# AD.net
KiCad netlist of a schematic drawn in Altium Designer
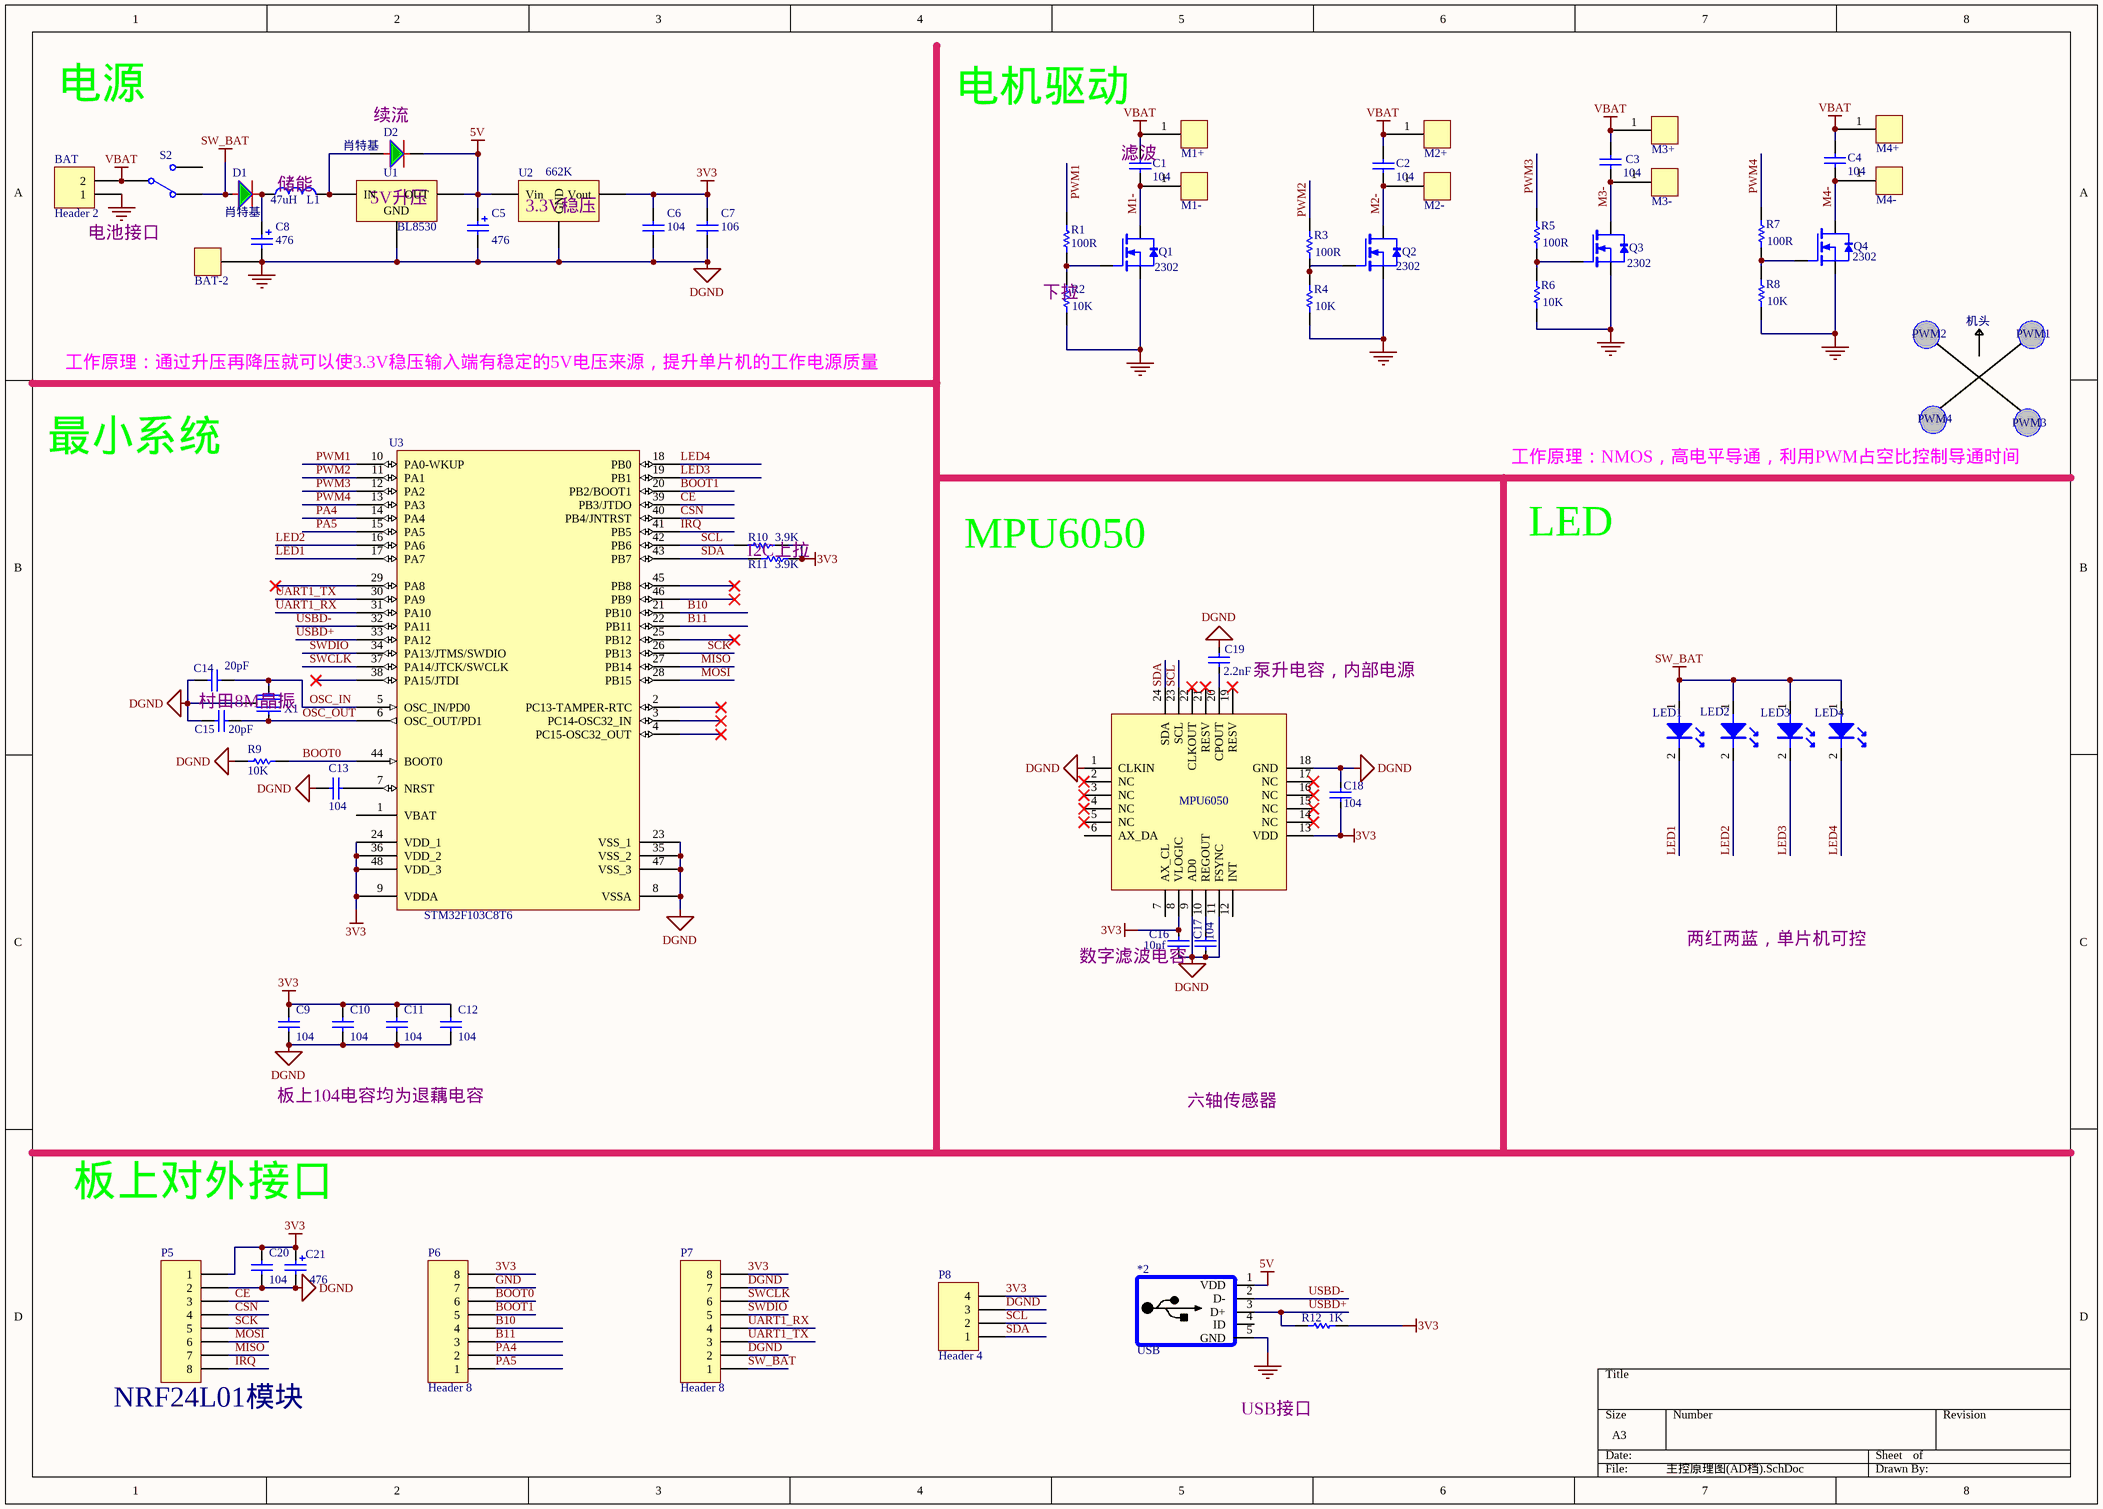
[diagram p0: 主控原理图(AD档).SchDoc]

(export (version "E")
  (design (tool "Eeschema 10.0.6"))
  (components
    (comp (ref "*2") (value "USB") (footprint "USB") (libsource (lib "电子鼓") (part "USB")))
    (comp (ref "BAT")
      (value "Header 2")
      (footprint "HDR2")
      (description "Header, 2-Pin")
      (fields (field (name "PUBLISHER") "Altium Limited"))
      (libsource (lib "Miscellaneous Connectors") (part "Header 2"))
    )
    (comp (ref "BAT-2") (value "Header 1") (footprint "电池接口") (libsource (lib "") (part "Header 1_1")))
    (comp (ref "C1")
      (value "104")
      (footprint "0603C")
      (description "Polarized Capacitor (Radial)")
      (fields (field (name "Comment") "Cap Chip 1206") (field (name "PUBLISHER") "Altium Limited"))
      (libsource (lib "ChapuIntegratedLibrary") (part "Cap Chip 1206"))
    )
    (comp (ref "C2")
      (value "104")
      (footprint "0603C")
      (description "Polarized Capacitor (Radial)")
      (fields (field (name "PUBLISHER") "Altium Limited"))
      (libsource (lib "ChapuIntegratedLibrary") (part "Cap Chip 1206"))
    )
    (comp (ref "C3")
      (value "104")
      (footprint "0603C")
      (description "Polarized Capacitor (Radial)")
      (fields (field (name "Comment") "Cap Chip 1206") (field (name "PUBLISHER") "Altium Limited"))
      (libsource (lib "ChapuIntegratedLibrary") (part "Cap Chip 1206"))
    )
    (comp (ref "C4")
      (value "104")
      (footprint "0603C")
      (description "Polarized Capacitor (Radial)")
      (fields (field (name "Comment") "Cap Chip 1206") (field (name "PUBLISHER") "Altium Limited"))
      (libsource (lib "ChapuIntegratedLibrary") (part "Cap Chip 1206"))
    )
    (comp (ref "C5")
      (value "476")
      (footprint "1206c")
      (description "Polarized Capacitor (Radial)")
      (fields
        (field (name "VOLTAGE") "16V")
        (field (name "Comment") "Cap Tan A")
        (field (name "PUBLISHER") "Altium Limited")
      )
      (libsource (lib "ChapuIntegratedLibrary") (part "Cap Tan A"))
    )
    (comp (ref "C6")
      (value "104")
      (footprint "0603C")
      (description "Polarized Capacitor (Radial)")
      (fields (field (name "Comment") "Cap Chip 1206") (field (name "PUBLISHER") "Altium Limited"))
      (libsource (lib "ChapuIntegratedLibrary") (part "Cap Chip 1206"))
    )
    (comp (ref "C7")
      (value "106")
      (footprint "0603c")
      (description "Polarized Capacitor (Radial)")
      (fields (field (name "Comment") "Cap Chip 1206") (field (name "PUBLISHER") "Altium Limited"))
      (libsource (lib "ChapuIntegratedLibrary") (part "Cap Chip 1206"))
    )
    (comp (ref "C8")
      (value "476")
      (footprint "1206c")
      (description "Polarized Capacitor (Radial)")
      (fields
        (field (name "VOLTAGE") "16V")
        (field (name "Comment") "Cap Tan A")
        (field (name "PUBLISHER") "Altium Limited")
      )
      (libsource (lib "ChapuIntegratedLibrary") (part "Cap Tan A"))
    )
    (comp (ref "C9") (value "104") (footprint "0603C") (libsource (lib "1218迷你四轴工程_1") (part "C0603")))
    (comp (ref "C10") (value "104") (footprint "0603C") (libsource (lib "1218迷你四轴工程_1") (part "C0603")))
    (comp (ref "C11") (value "104") (footprint "0603C") (libsource (lib "1218迷你四轴工程_1") (part "C0603")))
    (comp (ref "C12") (value "104") (footprint "0603C") (libsource (lib "1218迷你四轴工程_1") (part "C0603")))
    (comp (ref "C13") (value "104") (footprint "0603C") (libsource (lib "1218迷你四轴工程_1") (part "C0603")))
    (comp (ref "C14") (value "20pF") (footprint "0603C") (libsource (lib "1218迷你四轴工程_1") (part "C0603")))
    (comp (ref "C15") (value "20pF") (footprint "0603C") (libsource (lib "1218迷你四轴工程_1") (part "C0603")))
    (comp (ref "C16")
      (value "10nf")
      (footprint "0603C")
      (description "Capacitor")
      (fields (field (name "Comment") "Cap_0603"))
      (libsource (lib "SCH_Passive") (part "Cap_0603"))
    )
    (comp (ref "C17")
      (value "104")
      (footprint "0603C")
      (description "Capacitor")
      (fields (field (name "Comment") "Cap_0603"))
      (libsource (lib "SCH_Passive") (part "Cap_0603"))
    )
    (comp (ref "C18")
      (value "104")
      (footprint "0603C")
      (description "Capacitor")
      (fields (field (name "Comment") "Cap_0603"))
      (libsource (lib "SCH_Passive") (part "Cap_0603"))
    )
    (comp (ref "C19")
      (value "2.2nF")
      (footprint "0603C")
      (description "Capacitor")
      (fields (field (name "Comment") "Cap_0603"))
      (libsource (lib "SCH_Passive") (part "Cap_0603"))
    )
    (comp (ref "C20") (value "104") (footprint "0603C") (libsource (lib "1218迷你四轴工程_1") (part "C0603")))
    (comp (ref "C21")
      (value "476")
      (footprint "1206c")
      (description "Polarized Capacitor (Radial)")
      (fields
        (field (name "VOLTAGE") "16V")
        (field (name "Comment") "Cap Tan A")
        (field (name "PUBLISHER") "Altium Limited")
      )
      (libsource (lib "ChapuIntegratedLibrary") (part "Cap Tan A"))
    )
    (comp (ref "D1") (value "肖特基") (footprint "0805d") (libsource (lib "*") (part "DIODE")))
    (comp (ref "D2") (value "肖特基") (footprint "0805d") (libsource (lib "") (part "DIODE_1")))
    (comp (ref "L1")
      (value "47uH")
      (footprint "电感")
      (description "Inductor")
      (fields (field (name "Comment") "Inductor Chip") (field (name "PUBLISHER") "Altium Limited"))
      (libsource (lib "ChapuIntegratedLibrary") (part "Inductor Chip"))
    )
    (comp (ref "LED1") (value "LED") (footprint "0603D") (libsource (lib "1218迷你四轴工程_1") (part "LED")))
    (comp (ref "LED2") (value "LED") (footprint "0603D") (libsource (lib "1218迷你四轴工程_1") (part "LED")))
    (comp (ref "LED3") (value "LED") (footprint "0603D") (libsource (lib "1218迷你四轴工程_1") (part "LED")))
    (comp (ref "LED4") (value "LED") (footprint "0603D") (libsource (lib "1218迷你四轴工程_1") (part "LED")))
    (comp (ref "M1+") (value "Header 1") (footprint "电池接口") (libsource (lib "quadrotor") (part "Header 1")))
    (comp (ref "M1-") (value "Header 1") (footprint "电池接口") (libsource (lib "quadrotor") (part "Header 1")))
    (comp (ref "M2+") (value "Header 1") (footprint "电池接口") (libsource (lib "quadrotor") (part "Header 1")))
    (comp (ref "M2-") (value "Header 1") (footprint "电池接口") (libsource (lib "quadrotor") (part "Header 1")))
    (comp (ref "M3+") (value "Header 1") (footprint "电池接口") (libsource (lib "quadrotor") (part "Header 1")))
    (comp (ref "M3-") (value "Header 1") (footprint "电池接口") (libsource (lib "quadrotor") (part "Header 1")))
    (comp (ref "M4+") (value "Header 1") (footprint "电池接口") (libsource (lib "quadrotor") (part "Header 1")))
    (comp (ref "M4-") (value "Header 1") (footprint "电池接口") (libsource (lib "quadrotor") (part "Header 1")))
    (comp (ref "P5")
      (value "NRF24L01模块")
      (footprint "2.4G")
      (description "Header, 8-Pin")
      (fields (field (name "PUBLISHER") "Altium Limited"))
      (libsource (lib "Miscellaneous Connectors") (part "Header 8"))
    )
    (comp (ref "P6")
      (value "Header 8")
      (footprint "HDR8")
      (description "Header, 8-Pin")
      (fields (field (name "PUBLISHER") "Altium Limited"))
      (libsource (lib "") (part "Header 8_1"))
    )
    (comp (ref "P7")
      (value "Header 8")
      (footprint "HDR8")
      (description "Header, 8-Pin")
      (fields (field (name "PUBLISHER") "Altium Limited"))
      (libsource (lib "") (part "Header 8_1"))
    )
    (comp (ref "P8")
      (value "Header 4")
      (footprint "HDR4")
      (description "Header, 4-Pin")
      (fields (field (name "PUBLISHER") "Altium Limited"))
      (libsource (lib "Miscellaneous Connectors") (part "Header 4"))
    )
    (comp (ref "Q1")
      (value "2302")
      (footprint "NMOS")
      (description "N-Channel MOSFET")
      (libsource (lib "1218迷你四轴工程_1") (part "N_MOS"))
    )
    (comp (ref "Q2")
      (value "2302")
      (footprint "NMOS")
      (description "N-Channel Power MOSFET")
      (libsource (lib "1218迷你四轴工程_1") (part "N_MOS"))
    )
    (comp (ref "Q3")
      (value "2302")
      (footprint "NMOS")
      (description "N-Channel Power MOSFET")
      (libsource (lib "1218迷你四轴工程_1") (part "N_MOS"))
    )
    (comp (ref "Q4")
      (value "2302")
      (footprint "NMOS")
      (description "N-Channel Power MOSFET")
      (libsource (lib "1218迷你四轴工程_1") (part "N_MOS"))
    )
    (comp (ref "R1")
      (value "100R")
      (footprint "0603R")
      (description "Resistor")
      (fields (field (name "Comment") "Res1") (field (name "PUBLISHER") "Altium Limited"))
      (libsource (lib "Miscellaneous Devices") (part "Res1"))
    )
    (comp (ref "R2")
      (value "10K")
      (footprint "0603R")
      (description "Resistor")
      (fields (field (name "Comment") "Res1") (field (name "PUBLISHER") "Altium Limited"))
      (libsource (lib "Miscellaneous Devices") (part "Res1"))
    )
    (comp (ref "R3")
      (value "100R")
      (footprint "0603R")
      (description "Resistor")
      (fields (field (name "Comment") "Res1") (field (name "PUBLISHER") "Altium Limited"))
      (libsource (lib "Miscellaneous Devices") (part "Res1"))
    )
    (comp (ref "R4")
      (value "10K")
      (footprint "0603R")
      (description "Resistor")
      (fields (field (name "Comment") "Res1") (field (name "PUBLISHER") "Altium Limited"))
      (libsource (lib "Miscellaneous Devices") (part "Res1"))
    )
    (comp (ref "R5")
      (value "100R")
      (footprint "0603R")
      (description "Resistor")
      (fields (field (name "Comment") "Res1") (field (name "PUBLISHER") "Altium Limited"))
      (libsource (lib "Miscellaneous Devices") (part "Res1"))
    )
    (comp (ref "R6")
      (value "10K")
      (footprint "0603R")
      (description "Resistor")
      (fields (field (name "Comment") "Res1") (field (name "PUBLISHER") "Altium Limited"))
      (libsource (lib "Miscellaneous Devices") (part "Res1"))
    )
    (comp (ref "R7")
      (value "100R")
      (footprint "0603R")
      (description "Resistor")
      (fields (field (name "Comment") "Res1") (field (name "PUBLISHER") "Altium Limited"))
      (libsource (lib "Miscellaneous Devices") (part "Res1"))
    )
    (comp (ref "R8")
      (value "10K")
      (footprint "0603R")
      (description "Resistor")
      (fields (field (name "Comment") "Res1") (field (name "PUBLISHER") "Altium Limited"))
      (libsource (lib "Miscellaneous Devices") (part "Res1"))
    )
    (comp (ref "R9")
      (value "10K")
      (footprint "0603R")
      (description "Resistor")
      (fields (field (name "Comment") "Res1") (field (name "PUBLISHER") "Altium Limited"))
      (libsource (lib "Miscellaneous Devices") (part "Res1"))
    )
    (comp (ref "R10")
      (value "3.9K")
      (footprint "0603R")
      (description "Resistor")
      (fields (field (name "Comment") "Res1") (field (name "PUBLISHER") "Altium Limited"))
      (libsource (lib "Miscellaneous Devices") (part "Res1"))
    )
    (comp (ref "R11")
      (value "3.9K")
      (footprint "0603R")
      (description "Resistor")
      (fields (field (name "Comment") "Res1") (field (name "PUBLISHER") "Altium Limited"))
      (libsource (lib "Miscellaneous Devices") (part "Res1"))
    )
    (comp (ref "R12")
      (value "1K")
      (footprint "0603R")
      (description "Resistor")
      (fields (field (name "Comment") "Res1") (field (name "PUBLISHER") "Altium Limited"))
      (libsource (lib "Miscellaneous Devices") (part "Res1"))
    )
    (comp (ref "S2")
      (value "SW-SPDT")
      (footprint "SWITCH")
      (description "SPDT Subminiature Toggle Switch, Right Angle Mounting, Vertical Actuation")
      (fields (field (name "PUBLISHER") "Altium Limited"))
      (libsource (lib "Miscellaneous Devices") (part "SW-SPDT"))
    )
    (comp (ref "U1")
      (value "BL8530")
      (footprint "SOT-89")
      (description "POSITIVE OUTPUT VOLTAGE")
      (libsource (lib "Q222") (part "HT7750"))
    )
    (comp (ref "U2")
      (value "662K")
      (footprint "LDO")
      (description "3-Terminal Adjustable Positive Voltage Regulator")
      (libsource (lib "稳压器件") (part "LM317"))
    )
    (comp (ref "U3")
      (value "STM32F103C8T6")
      (footprint "LQFP48")
      (libsource (lib "微型四轴") (part "STM32F103C8T6"))
    )
    (comp (ref "U8") (value "MPU6050") (footprint "QFN24") (libsource (lib "1218迷你四轴工程_1") (part "MPU6050")))
    (comp (ref "X1") (value "XTAL_SMT") (footprint "OSC") (libsource (lib "dx原理图库") (part "XTAL_SMT")))
  )
  (nets
    (net (code "1") (name "/B10") (class "Default")
      (node (ref "P6") (pin "4") (pinfunction "4_4") (pintype "passive"))
      (node (ref "U3") (pin "21") (pinfunction "PB10_21") (pintype "bidirectional"))
    )
    (net (code "2") (name "/B11") (class "Default")
      (node (ref "P6") (pin "3") (pinfunction "3_3") (pintype "passive"))
      (node (ref "U3") (pin "22") (pinfunction "PB11_22") (pintype "bidirectional"))
    )
    (net (code "3") (name "/BOOT0") (class "Default")
      (node (ref "P6") (pin "6") (pinfunction "6_6") (pintype "passive"))
      (node (ref "R9") (pin "1") (pinfunction "1_1") (pintype "passive"))
      (node (ref "U3") (pin "44") (pinfunction "BOOT0_44") (pintype "input"))
    )
    (net (code "4") (name "/BOOT1") (class "Default")
      (node (ref "P6") (pin "5") (pinfunction "5_5") (pintype "passive"))
      (node (ref "U3") (pin "20") (pinfunction "PB2/BOOT1_20") (pintype "bidirectional"))
    )
    (net (code "5") (name "/CE") (class "Default")
      (node (ref "P5") (pin "3") (pinfunction "3_3") (pintype "passive"))
      (node (ref "U3") (pin "39") (pinfunction "PB3/JTDO_39") (pintype "bidirectional"))
    )
    (net (code "6") (name "/CSN") (class "Default")
      (node (ref "P5") (pin "4") (pinfunction "4_4") (pintype "passive"))
      (node (ref "U3") (pin "40") (pinfunction "PB4/JNTRST_40") (pintype "bidirectional"))
    )
    (net (code "7") (name "/IRQ") (class "Default")
      (node (ref "P5") (pin "8") (pinfunction "8_8") (pintype "passive"))
      (node (ref "U3") (pin "41") (pinfunction "PB5_41") (pintype "bidirectional"))
    )
    (net (code "8") (name "/LED1") (class "Default")
      (node (ref "LED1") (pin "2") (pinfunction "2_2") (pintype "passive"))
      (node (ref "U3") (pin "17") (pinfunction "PA7_17") (pintype "bidirectional"))
    )
    (net (code "9") (name "/LED2") (class "Default")
      (node (ref "LED2") (pin "2") (pinfunction "2_2") (pintype "passive"))
      (node (ref "U3") (pin "16") (pinfunction "PA6_16") (pintype "bidirectional"))
    )
    (net (code "10") (name "/LED3") (class "Default")
      (node (ref "LED3") (pin "2") (pinfunction "2_2") (pintype "passive"))
      (node (ref "U3") (pin "19") (pinfunction "PB1_19") (pintype "bidirectional"))
    )
    (net (code "11") (name "/LED4") (class "Default")
      (node (ref "LED4") (pin "2") (pinfunction "2_2") (pintype "passive"))
      (node (ref "U3") (pin "18") (pinfunction "PB0_18") (pintype "bidirectional"))
    )
    (net (code "12") (name "/M1-") (class "Default")
      (node (ref "C1") (pin "1") (pinfunction "1_1") (pintype "passive"))
      (node (ref "M1-") (pin "1") (pintype "passive"))
      (node (ref "Q1") (pin "2") (pinfunction "D_2") (pintype "passive"))
    )
    (net (code "13") (name "/M2-") (class "Default")
      (node (ref "C2") (pin "1") (pinfunction "1_1") (pintype "passive"))
      (node (ref "M2-") (pin "1") (pintype "passive"))
      (node (ref "Q2") (pin "2") (pinfunction "D_2") (pintype "passive"))
    )
    (net (code "14") (name "/M3-") (class "Default")
      (node (ref "C3") (pin "1") (pinfunction "1_1") (pintype "passive"))
      (node (ref "M3-") (pin "1") (pintype "passive"))
      (node (ref "Q3") (pin "2") (pinfunction "D_2") (pintype "passive"))
    )
    (net (code "15") (name "/M4-") (class "Default")
      (node (ref "C4") (pin "1") (pinfunction "1_1") (pintype "passive"))
      (node (ref "M4-") (pin "1") (pintype "passive"))
      (node (ref "Q4") (pin "2") (pinfunction "D_2") (pintype "passive"))
    )
    (net (code "16") (name "/MISO") (class "Default")
      (node (ref "P5") (pin "7") (pinfunction "7_7") (pintype "passive"))
      (node (ref "U3") (pin "27") (pinfunction "PB14_27") (pintype "bidirectional"))
    )
    (net (code "17") (name "/MOSI") (class "Default")
      (node (ref "P5") (pin "6") (pinfunction "6_6") (pintype "passive"))
      (node (ref "U3") (pin "28") (pinfunction "PB15_28") (pintype "bidirectional"))
    )
    (net (code "18") (name "/OSC_IN") (class "Default")
      (node (ref "C14") (pin "1") (pinfunction "1_1") (pintype "passive"))
      (node (ref "U3") (pin "5") (pinfunction "OSC_IN/PD0_5") (pintype "input"))
      (node (ref "X1") (pin "2") (pintype "passive"))
    )
    (net (code "19") (name "/OSC_OUT") (class "Default")
      (node (ref "C15") (pin "1") (pinfunction "1_1") (pintype "passive"))
      (node (ref "U3") (pin "6") (pinfunction "OSC_OUT/PD1_6") (pintype "output"))
      (node (ref "X1") (pin "1") (pintype "passive"))
    )
    (net (code "20") (name "/PA4") (class "Default")
      (node (ref "P6") (pin "2") (pinfunction "2_2") (pintype "passive"))
      (node (ref "U3") (pin "14") (pinfunction "PA4_14") (pintype "bidirectional"))
    )
    (net (code "21") (name "/PA5") (class "Default")
      (node (ref "P6") (pin "1") (pinfunction "1_1") (pintype "passive"))
      (node (ref "U3") (pin "15") (pinfunction "PA5_15") (pintype "bidirectional"))
    )
    (net (code "22") (name "/PWM1") (class "Default")
      (node (ref "R1") (pin "2") (pinfunction "2_2") (pintype "passive"))
      (node (ref "U3") (pin "10") (pinfunction "PA0-WKUP_10") (pintype "bidirectional"))
    )
    (net (code "23") (name "/PWM2") (class "Default")
      (node (ref "R3") (pin "2") (pinfunction "2_2") (pintype "passive"))
      (node (ref "U3") (pin "11") (pinfunction "PA1_11") (pintype "bidirectional"))
    )
    (net (code "24") (name "/PWM3") (class "Default")
      (node (ref "R5") (pin "2") (pinfunction "2_2") (pintype "passive"))
      (node (ref "U3") (pin "12") (pinfunction "PA2_12") (pintype "bidirectional"))
    )
    (net (code "25") (name "/PWM4") (class "Default")
      (node (ref "R7") (pin "2") (pinfunction "2_2") (pintype "passive"))
      (node (ref "U3") (pin "13") (pinfunction "PA3_13") (pintype "bidirectional"))
    )
    (net (code "26") (name "/SCK") (class "Default")
      (node (ref "P5") (pin "5") (pinfunction "5_5") (pintype "passive"))
      (node (ref "U3") (pin "26") (pinfunction "PB13_26") (pintype "bidirectional"))
    )
    (net (code "27") (name "/SCL") (class "Default")
      (node (ref "P8") (pin "2") (pinfunction "2_2") (pintype "passive"))
      (node (ref "R10") (pin "2") (pinfunction "2_2") (pintype "passive"))
      (node (ref "U3") (pin "42") (pinfunction "PB6_42") (pintype "bidirectional"))
      (node (ref "U8") (pin "23") (pinfunction "SCL_23") (pintype "passive"))
    )
    (net (code "28") (name "/SDA") (class "Default")
      (node (ref "P8") (pin "1") (pinfunction "1_1") (pintype "passive"))
      (node (ref "R11") (pin "2") (pinfunction "2_2") (pintype "passive"))
      (node (ref "U3") (pin "43") (pinfunction "PB7_43") (pintype "bidirectional"))
      (node (ref "U8") (pin "24") (pinfunction "SDA_24") (pintype "passive"))
    )
    (net (code "29") (name "/SWCLK") (class "Default")
      (node (ref "P7") (pin "6") (pinfunction "6_6") (pintype "passive"))
      (node (ref "U3") (pin "37") (pinfunction "PA14/JTCK/SWCLK_37") (pintype "bidirectional"))
    )
    (net (code "30") (name "/SWDIO") (class "Default")
      (node (ref "P7") (pin "5") (pinfunction "5_5") (pintype "passive"))
      (node (ref "U3") (pin "34") (pinfunction "PA13/JTMS/SWDIO_34") (pintype "bidirectional"))
    )
    (net (code "31") (name "/UART1_RX") (class "Default")
      (node (ref "P7") (pin "4") (pinfunction "4_4") (pintype "passive"))
      (node (ref "U3") (pin "31") (pinfunction "PA10_31") (pintype "bidirectional"))
    )
    (net (code "32") (name "/UART1_TX") (class "Default")
      (node (ref "P7") (pin "3") (pinfunction "3_3") (pintype "passive"))
      (node (ref "U3") (pin "30") (pinfunction "PA9_30") (pintype "bidirectional"))
    )
    (net (code "33") (name "/USBD+") (class "Default")
      (node (ref "*2") (pin "3") (pinfunction "D+_3") (pintype "passive"))
      (node (ref "R12") (pin "2") (pinfunction "2_2") (pintype "passive"))
      (node (ref "U3") (pin "33") (pinfunction "PA12_33") (pintype "bidirectional"))
    )
    (net (code "34") (name "/USBD-") (class "Default")
      (node (ref "*2") (pin "2") (pinfunction "D-_2") (pintype "passive"))
      (node (ref "U3") (pin "32") (pinfunction "PA11_32") (pintype "bidirectional"))
    )
    (net (code "35") (name "3V3") (class "Default")
      (node (ref "C10") (pin "1") (pinfunction "1_1") (pintype "passive"))
      (node (ref "C11") (pin "1") (pinfunction "1_1") (pintype "passive"))
      (node (ref "C12") (pin "1") (pinfunction "1_1") (pintype "passive"))
      (node (ref "C16") (pin "2") (pinfunction "2_2") (pintype "passive"))
      (node (ref "C18") (pin "1") (pinfunction "1_1") (pintype "passive"))
      (node (ref "C20") (pin "1") (pinfunction "1_1") (pintype "passive"))
      (node (ref "C21") (pin "2") (pinfunction "1_2") (pintype "passive"))
      (node (ref "C6") (pin "1") (pinfunction "1_1") (pintype "passive"))
      (node (ref "C7") (pin "1") (pinfunction "1_1") (pintype "passive"))
      (node (ref "C9") (pin "1") (pinfunction "1_1") (pintype "passive"))
      (node (ref "P5") (pin "1") (pinfunction "1_1") (pintype "passive"))
      (node (ref "P6") (pin "8") (pinfunction "8_8") (pintype "passive"))
      (node (ref "P7") (pin "8") (pinfunction "8_8") (pintype "passive"))
      (node (ref "P8") (pin "4") (pinfunction "4_4") (pintype "passive"))
      (node (ref "R10") (pin "1") (pinfunction "1_1") (pintype "passive"))
      (node (ref "R11") (pin "1") (pinfunction "1_1") (pintype "passive"))
      (node (ref "R12") (pin "1") (pinfunction "1_1") (pintype "passive"))
      (node (ref "U2") (pin "2") (pinfunction "Vout_2") (pintype "passive"))
      (node (ref "U3") (pin "24") (pinfunction "VDD_1_24") (pintype "power_in"))
      (node (ref "U3") (pin "36") (pinfunction "VDD_2_36") (pintype "power_in"))
      (node (ref "U3") (pin "48") (pinfunction "VDD_3_48") (pintype "power_in"))
      (node (ref "U3") (pin "9") (pinfunction "VDDA_9") (pintype "power_in"))
      (node (ref "U8") (pin "13") (pinfunction "VDD_13") (pintype "passive"))
      (node (ref "U8") (pin "8") (pinfunction "VLOGIC_8") (pintype "passive"))
    )
    (net (code "36") (name "5V") (class "Default")
      (node (ref "*2") (pin "1") (pinfunction "VDD_1") (pintype "passive"))
      (node (ref "C5") (pin "2") (pinfunction "1_2") (pintype "passive"))
      (node (ref "D2") (pin "2") (pinfunction "2_2") (pintype "passive"))
      (node (ref "U1") (pin "2") (pinfunction "OUT_2") (pintype "power_in"))
      (node (ref "U2") (pin "3") (pinfunction "Vin_3") (pintype "passive"))
    )
    (net (code "37") (name "DGND") (class "Default")
      (node (ref "*2") (pin "5") (pinfunction "GND_5") (pintype "passive"))
      (node (ref "BAT") (pin "1") (pinfunction "1_1") (pintype "passive"))
      (node (ref "BAT-2") (pin "1") (pintype "passive"))
      (node (ref "C10") (pin "2") (pinfunction "2_2") (pintype "passive"))
      (node (ref "C11") (pin "2") (pinfunction "2_2") (pintype "passive"))
      (node (ref "C12") (pin "2") (pinfunction "2_2") (pintype "passive"))
      (node (ref "C13") (pin "1") (pinfunction "1_1") (pintype "passive"))
      (node (ref "C14") (pin "2") (pinfunction "2_2") (pintype "passive"))
      (node (ref "C15") (pin "2") (pinfunction "2_2") (pintype "passive"))
      (node (ref "C16") (pin "1") (pinfunction "1_1") (pintype "passive"))
      (node (ref "C17") (pin "1") (pinfunction "1_1") (pintype "passive"))
      (node (ref "C18") (pin "2") (pinfunction "2_2") (pintype "passive"))
      (node (ref "C19") (pin "2") (pinfunction "2_2") (pintype "passive"))
      (node (ref "C20") (pin "2") (pinfunction "2_2") (pintype "passive"))
      (node (ref "C21") (pin "1") (pinfunction "2_1") (pintype "passive"))
      (node (ref "C5") (pin "1") (pinfunction "2_1") (pintype "passive"))
      (node (ref "C6") (pin "2") (pinfunction "2_2") (pintype "passive"))
      (node (ref "C7") (pin "2") (pinfunction "2_2") (pintype "passive"))
      (node (ref "C8") (pin "1") (pinfunction "2_1") (pintype "passive"))
      (node (ref "C9") (pin "2") (pinfunction "2_2") (pintype "passive"))
      (node (ref "P5") (pin "2") (pinfunction "2_2") (pintype "passive"))
      (node (ref "P6") (pin "7") (pinfunction "7_7") (pintype "passive"))
      (node (ref "P7") (pin "2") (pinfunction "2_2") (pintype "passive"))
      (node (ref "P7") (pin "7") (pinfunction "7_7") (pintype "passive"))
      (node (ref "P8") (pin "3") (pinfunction "3_3") (pintype "passive"))
      (node (ref "Q1") (pin "3") (pinfunction "S_3") (pintype "passive"))
      (node (ref "Q2") (pin "3") (pinfunction "S_3") (pintype "passive"))
      (node (ref "Q3") (pin "3") (pinfunction "S_3") (pintype "passive"))
      (node (ref "Q4") (pin "3") (pinfunction "S_3") (pintype "passive"))
      (node (ref "R2") (pin "1") (pinfunction "1_1") (pintype "passive"))
      (node (ref "R4") (pin "1") (pinfunction "1_1") (pintype "passive"))
      (node (ref "R6") (pin "1") (pinfunction "1_1") (pintype "passive"))
      (node (ref "R8") (pin "1") (pinfunction "1_1") (pintype "passive"))
      (node (ref "R9") (pin "2") (pinfunction "2_2") (pintype "passive"))
      (node (ref "U1") (pin "1") (pinfunction "GND_1") (pintype "power_in"))
      (node (ref "U2") (pin "1") (pinfunction "GND_1") (pintype "passive"))
      (node (ref "U3") (pin "23") (pinfunction "VSS_1_23") (pintype "power_in"))
      (node (ref "U3") (pin "35") (pinfunction "VSS_2_35") (pintype "power_in"))
      (node (ref "U3") (pin "47") (pinfunction "VSS_3_47") (pintype "power_in"))
      (node (ref "U3") (pin "8") (pinfunction "VSSA_8") (pintype "power_in"))
      (node (ref "U8") (pin "1") (pinfunction "CLKIN_1") (pintype "passive"))
      (node (ref "U8") (pin "11") (pinfunction "FSYNC_11") (pintype "passive"))
      (node (ref "U8") (pin "18") (pinfunction "GND_18") (pintype "passive"))
      (node (ref "U8") (pin "9") (pinfunction "AD0_9") (pintype "passive"))
      (node (ref "X1") (pin "0") (pinfunction "0_0") (pintype "passive"))
    )
    (net (code "38") (name "Net-(C8-1)") (class "Default")
      (node (ref "C8") (pin "2") (pinfunction "1_2") (pintype "passive"))
      (node (ref "D1") (pin "2") (pinfunction "2_2") (pintype "passive"))
      (node (ref "L1") (pin "1") (pinfunction "1_1") (pintype "passive"))
    )
    (net (code "39") (name "Net-(Q1-G)") (class "Default")
      (node (ref "Q1") (pin "1") (pinfunction "G_1") (pintype "passive"))
      (node (ref "R1") (pin "1") (pinfunction "1_1") (pintype "passive"))
      (node (ref "R2") (pin "2") (pinfunction "2_2") (pintype "passive"))
    )
    (net (code "40") (name "Net-(Q2-G)") (class "Default")
      (node (ref "Q2") (pin "1") (pinfunction "G_1") (pintype "passive"))
      (node (ref "R3") (pin "1") (pinfunction "1_1") (pintype "passive"))
      (node (ref "R4") (pin "2") (pinfunction "2_2") (pintype "passive"))
    )
    (net (code "41") (name "Net-(Q3-G)") (class "Default")
      (node (ref "Q3") (pin "1") (pinfunction "G_1") (pintype "passive"))
      (node (ref "R5") (pin "1") (pinfunction "1_1") (pintype "passive"))
      (node (ref "R6") (pin "2") (pinfunction "2_2") (pintype "passive"))
    )
    (net (code "42") (name "Net-(Q4-G)") (class "Default")
      (node (ref "Q4") (pin "1") (pinfunction "G_1") (pintype "passive"))
      (node (ref "R7") (pin "1") (pinfunction "1_1") (pintype "passive"))
      (node (ref "R8") (pin "2") (pinfunction "2_2") (pintype "passive"))
    )
    (net (code "43") (name "Net-(U1-IN)") (class "Default")
      (node (ref "D2") (pin "1") (pinfunction "1_1") (pintype "passive"))
      (node (ref "L1") (pin "2") (pinfunction "2_2") (pintype "passive"))
      (node (ref "U1") (pin "3") (pinfunction "IN_3") (pintype "power_in"))
    )
    (net (code "44") (name "Net-(U3-NRST)") (class "Default")
      (node (ref "C13") (pin "2") (pinfunction "2_2") (pintype "passive"))
      (node (ref "U3") (pin "7") (pinfunction "NRST_7") (pintype "bidirectional"))
    )
    (net (code "45") (name "Net-(U8-CPOUT)") (class "Default")
      (node (ref "C19") (pin "1") (pinfunction "1_1") (pintype "passive"))
      (node (ref "U8") (pin "20") (pinfunction "CPOUT_20") (pintype "passive"))
    )
    (net (code "46") (name "Net-(U8-REGOUT)") (class "Default")
      (node (ref "C17") (pin "2") (pinfunction "2_2") (pintype "passive"))
      (node (ref "U8") (pin "10") (pinfunction "REGOUT_10") (pintype "passive"))
    )
    (net (code "47") (name "SW_BAT") (class "Default")
      (node (ref "D1") (pin "1") (pinfunction "1_1") (pintype "passive"))
      (node (ref "LED1") (pin "1") (pinfunction "1_1") (pintype "passive"))
      (node (ref "LED2") (pin "1") (pinfunction "1_1") (pintype "passive"))
      (node (ref "LED3") (pin "1") (pinfunction "1_1") (pintype "passive"))
      (node (ref "LED4") (pin "1") (pinfunction "1_1") (pintype "passive"))
      (node (ref "P7") (pin "1") (pinfunction "1_1") (pintype "passive"))
      (node (ref "S2") (pin "3") (pinfunction "3_3") (pintype "passive"))
    )
    (net (code "48") (name "VBAT") (class "Default")
      (node (ref "BAT") (pin "2") (pinfunction "2_2") (pintype "passive"))
      (node (ref "C1") (pin "2") (pinfunction "2_2") (pintype "passive"))
      (node (ref "C2") (pin "2") (pinfunction "2_2") (pintype "passive"))
      (node (ref "C3") (pin "2") (pinfunction "2_2") (pintype "passive"))
      (node (ref "C4") (pin "2") (pinfunction "2_2") (pintype "passive"))
      (node (ref "M1+") (pin "1") (pintype "passive"))
      (node (ref "M2+") (pin "1") (pintype "passive"))
      (node (ref "M3+") (pin "1") (pintype "passive"))
      (node (ref "M4+") (pin "1") (pintype "passive"))
      (node (ref "S2") (pin "2") (pinfunction "2_2") (pintype "passive"))
    )
    (net (code "49") (name "unconnected-(*2-ID-Pad4)") (class "Default")
      (node (ref "*2") (pin "4") (pinfunction "ID_4") (pintype "passive"))
    )
    (net (code "50") (name "unconnected-(S2-Pad1)") (class "Default")
      (node (ref "S2") (pin "1") (pinfunction "1_1") (pintype "passive"))
    )
    (net (code "51") (name "unconnected-(U3-PA8-Pad29)") (class "Default")
      (node (ref "U3") (pin "29") (pinfunction "PA8_29") (pintype "bidirectional+no_connect"))
    )
    (net (code "52") (name "unconnected-(U3-PA15{slash}JTDI-Pad38)") (class "Default")
      (node (ref "U3") (pin "38") (pinfunction "PA15/JTDI_38") (pintype "bidirectional+no_connect"))
    )
    (net (code "53") (name "unconnected-(U3-PB8-Pad45)") (class "Default")
      (node (ref "U3") (pin "45") (pinfunction "PB8_45") (pintype "bidirectional+no_connect"))
    )
    (net (code "54") (name "unconnected-(U3-PB9-Pad46)") (class "Default")
      (node (ref "U3") (pin "46") (pinfunction "PB9_46") (pintype "bidirectional+no_connect"))
    )
    (net (code "55") (name "unconnected-(U3-PB12-Pad25)") (class "Default")
      (node (ref "U3") (pin "25") (pinfunction "PB12_25") (pintype "bidirectional+no_connect"))
    )
    (net (code "56") (name "unconnected-(U3-PC13-TAMPER-RTC-Pad2)") (class "Default")
      (node (ref "U3") (pin "2") (pinfunction "PC13-TAMPER-RTC_2") (pintype "bidirectional+no_connect"))
    )
    (net (code "57") (name "unconnected-(U3-PC14-OSC32_IN-Pad3)") (class "Default")
      (node (ref "U3") (pin "3") (pinfunction "PC14-OSC32_IN_3") (pintype "bidirectional+no_connect"))
    )
    (net (code "58") (name "unconnected-(U3-PC15-OSC32_OUT-Pad4)") (class "Default")
      (node (ref "U3") (pin "4") (pinfunction "PC15-OSC32_OUT_4") (pintype "bidirectional+no_connect"))
    )
    (net (code "59") (name "unconnected-(U3-VBAT-Pad1)") (class "Default")
      (node (ref "U3") (pin "1") (pinfunction "VBAT_1") (pintype "power_in"))
    )
    (net (code "60") (name "unconnected-(U8-AX_CL-Pad7)") (class "Default")
      (node (ref "U8") (pin "7") (pinfunction "AX_CL_7") (pintype "passive"))
    )
    (net (code "61") (name "unconnected-(U8-AX_DA-Pad6)") (class "Default")
      (node (ref "U8") (pin "6") (pinfunction "AX_DA_6") (pintype "passive"))
    )
    (net (code "62") (name "unconnected-(U8-CLKOUT-Pad22)") (class "Default")
      (node (ref "U8") (pin "22") (pinfunction "CLKOUT_22") (pintype "passive+no_connect"))
    )
    (net (code "63") (name "unconnected-(U8-INT-Pad12)") (class "Default")
      (node (ref "U8") (pin "12") (pinfunction "INT_12") (pintype "passive"))
    )
    (net (code "64") (name "unconnected-(U8-NC-Pad2)") (class "Default")
      (node (ref "U8") (pin "2") (pinfunction "NC_2") (pintype "passive+no_connect"))
    )
    (net (code "65") (name "unconnected-(U8-NC-Pad3)") (class "Default")
      (node (ref "U8") (pin "3") (pinfunction "NC_3") (pintype "passive+no_connect"))
    )
    (net (code "66") (name "unconnected-(U8-NC-Pad4)") (class "Default")
      (node (ref "U8") (pin "4") (pinfunction "NC_4") (pintype "passive+no_connect"))
    )
    (net (code "67") (name "unconnected-(U8-NC-Pad5)") (class "Default")
      (node (ref "U8") (pin "5") (pinfunction "NC_5") (pintype "passive+no_connect"))
    )
    (net (code "68") (name "unconnected-(U8-NC-Pad14)") (class "Default")
      (node (ref "U8") (pin "14") (pinfunction "NC_14") (pintype "passive+no_connect"))
    )
    (net (code "69") (name "unconnected-(U8-NC-Pad15)") (class "Default")
      (node (ref "U8") (pin "15") (pinfunction "NC_15") (pintype "passive+no_connect"))
    )
    (net (code "70") (name "unconnected-(U8-NC-Pad16)") (class "Default")
      (node (ref "U8") (pin "16") (pinfunction "NC_16") (pintype "passive+no_connect"))
    )
    (net (code "71") (name "unconnected-(U8-NC-Pad17)") (class "Default")
      (node (ref "U8") (pin "17") (pinfunction "NC_17") (pintype "passive+no_connect"))
    )
    (net (code "72") (name "unconnected-(U8-RESV-Pad19)") (class "Default")
      (node (ref "U8") (pin "19") (pinfunction "RESV_19") (pintype "passive+no_connect"))
    )
    (net (code "73") (name "unconnected-(U8-RESV-Pad21)") (class "Default")
      (node (ref "U8") (pin "21") (pinfunction "RESV_21") (pintype "passive+no_connect"))
    )
  )
)
